# schematicEagle.net
KiCad netlist of a schematic drawn in EAGLE
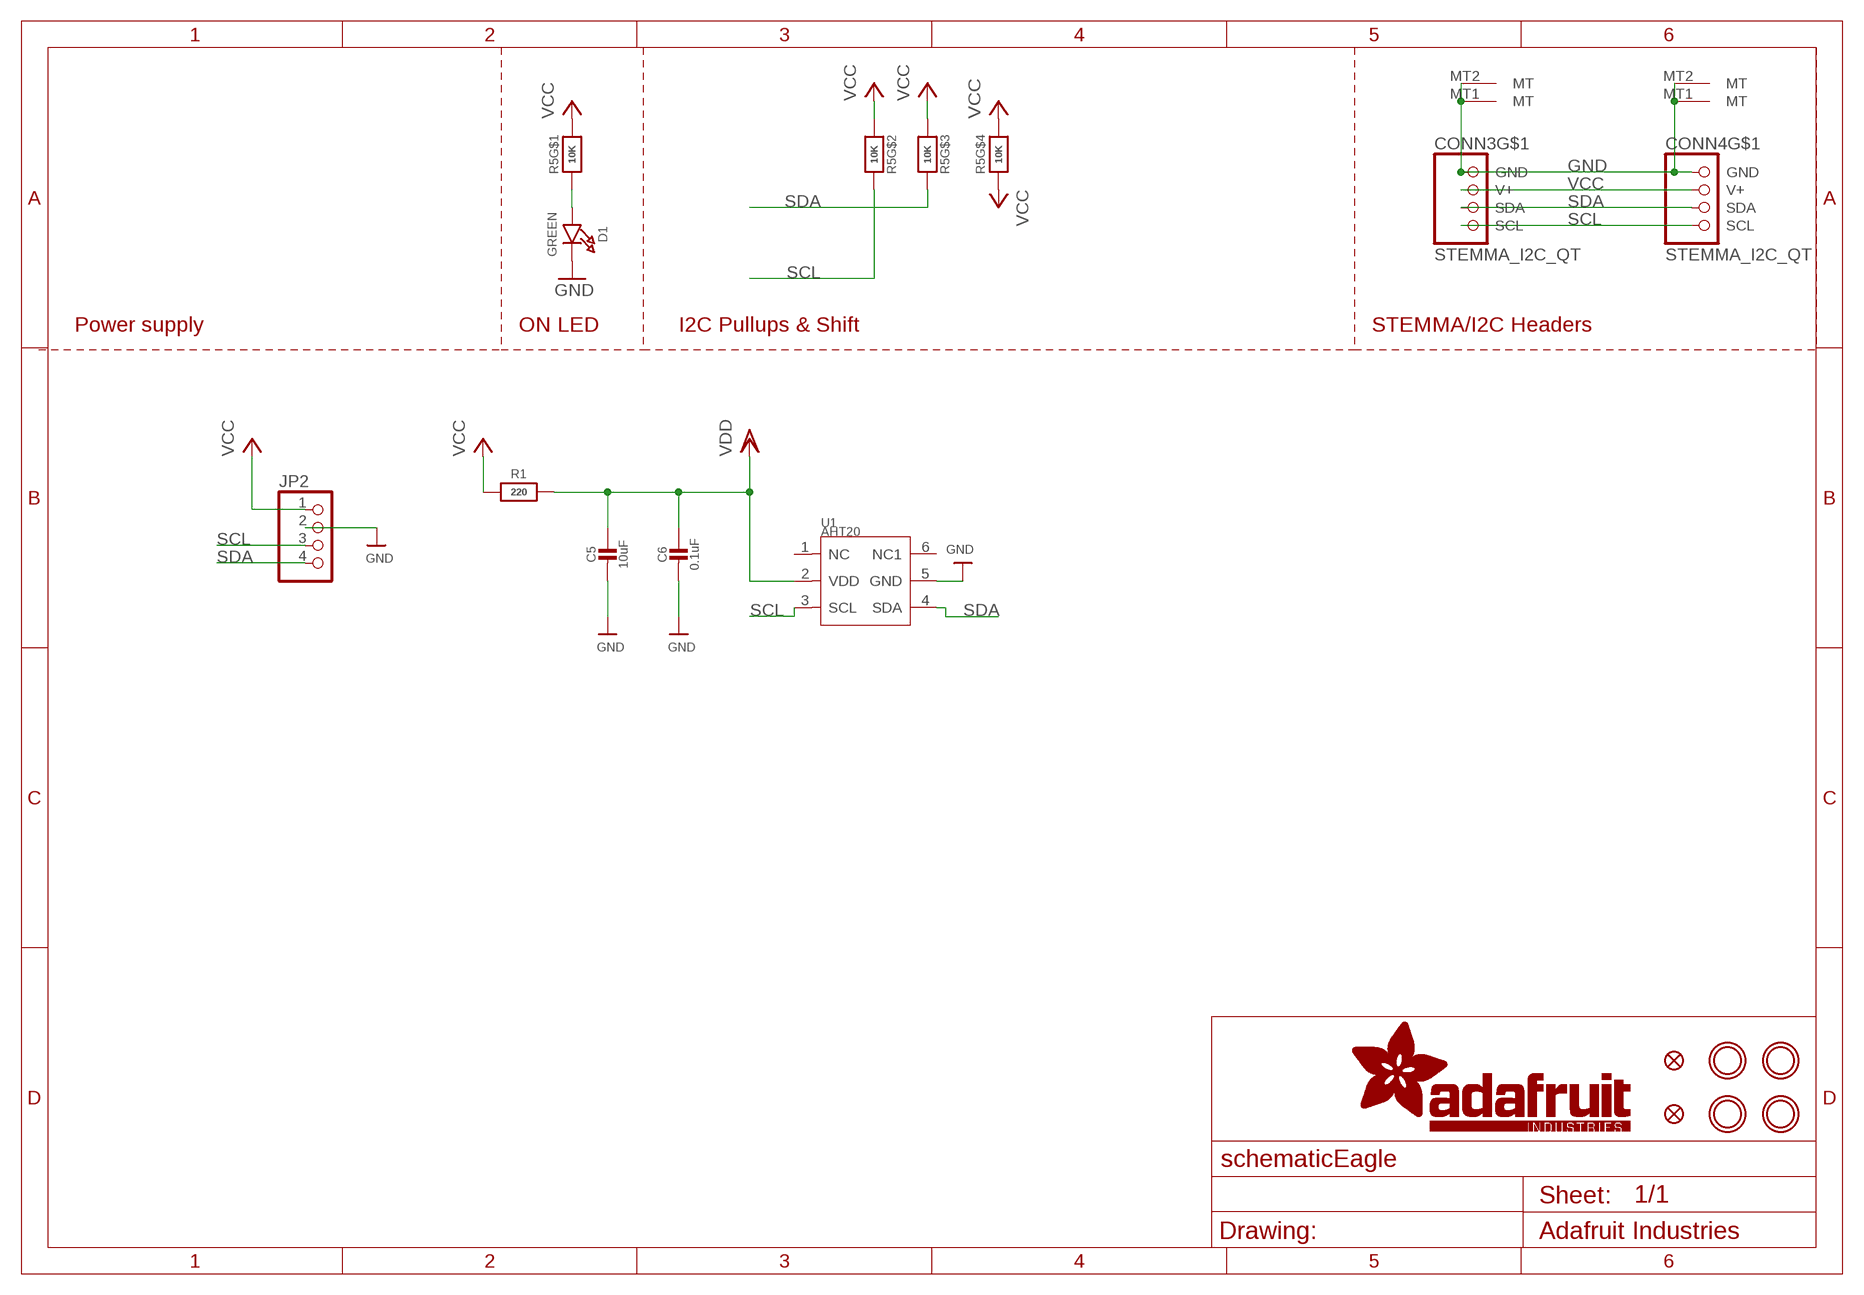
[diagram p0: schematic, sheet 1]

(export (version "E")
  (design (tool "Eeschema 10.0.6"))
  (components
    (comp (ref "C5")
      (value "10uF")
      (footprint "eagle-import:0805-NO")
      (libsource (lib "eagle-import") (part "CAP_CERAMIC0805-NOOUTLINE"))
    )
    (comp (ref "C6")
      (value "0.1uF")
      (footprint "eagle-import:0603-NO")
      (libsource (lib "eagle-import") (part "CAP_CERAMIC0603_NO"))
    )
    (comp (ref "CONN3")
      (value "STEMMA_I2C_QT")
      (footprint "eagle-import:JST_SH4")
      (libsource (lib "eagle-import") (part "STEMMA_I2C_QT"))
    )
    (comp (ref "CONN4")
      (value "STEMMA_I2C_QT")
      (footprint "eagle-import:JST_SH4")
      (libsource (lib "eagle-import") (part "STEMMA_I2C_QT"))
    )
    (comp (ref "D1")
      (value "GREEN")
      (footprint "eagle-import:CHIPLED_0603_NOOUTLINE")
      (libsource (lib "eagle-import") (part "LED0603_NOOUTLINE"))
    )
    (comp (ref "FID3")
      (value "FIDUCIAL_1MM")
      (footprint "eagle-import:FIDUCIAL_1MM")
      (libsource (lib "eagle-import") (part "FIDUCIAL_1MM"))
    )
    (comp (ref "FID4")
      (value "FIDUCIAL_1MM")
      (footprint "eagle-import:FIDUCIAL_1MM")
      (libsource (lib "eagle-import") (part "FIDUCIAL_1MM"))
    )
    (comp (ref "JP2")
      (value "HEADER-1X476MIL")
      (footprint "eagle-import:1X04_ROUND_76")
      (libsource (lib "eagle-import") (part "HEADER-1X476MIL"))
    )
    (comp (ref "R1")
      (value "220")
      (footprint "eagle-import:0603-NO")
      (libsource (lib "eagle-import") (part "RESISTOR_0603_NOOUT"))
    )
    (comp (ref "R5")
      (value "10K")
      (footprint "eagle-import:RESPACK_4X0603")
      (libsource (lib "eagle-import") (part "RESISTOR_4PACK"))
    )
    (comp (ref "U$19")
      (value "MOUNTINGHOLE2.5")
      (footprint "eagle-import:MOUNTINGHOLE_2.5_PLATED")
      (libsource (lib "eagle-import") (part "MOUNTINGHOLE2.5"))
    )
    (comp (ref "U$20")
      (value "MOUNTINGHOLE2.5")
      (footprint "eagle-import:MOUNTINGHOLE_2.5_PLATED")
      (libsource (lib "eagle-import") (part "MOUNTINGHOLE2.5"))
    )
    (comp (ref "U$22")
      (value "MOUNTINGHOLE2.5")
      (footprint "eagle-import:MOUNTINGHOLE_2.5_PLATED")
      (libsource (lib "eagle-import") (part "MOUNTINGHOLE2.5"))
    )
    (comp (ref "U$25")
      (value "MOUNTINGHOLE2.5")
      (footprint "eagle-import:MOUNTINGHOLE_2.5_PLATED")
      (libsource (lib "eagle-import") (part "MOUNTINGHOLE2.5"))
    )
    (comp (ref "U1")
      (value "AHT20")
      (footprint "eagle-import:SNR6-1.0-3X3X1MM")
      (libsource (lib "eagle-import") (part "SENSOR-AHT20"))
    )
  )
  (nets
    (net (code "1") (name "/SCL") (class "Default")
      (node (ref "CONN3") (pin "4") (pinfunction "SCL_4") (pintype "passive"))
      (node (ref "CONN4") (pin "4") (pinfunction "SCL_4") (pintype "passive"))
      (node (ref "JP2") (pin "3") (pinfunction "3_3") (pintype "passive"))
      (node (ref "R5") (pin "7") (pinfunction "2_7") (pintype "passive"))
      (node (ref "U1") (pin "3") (pinfunction "SCL_3") (pintype "bidirectional"))
    )
    (net (code "2") (name "/SDA") (class "Default")
      (node (ref "CONN3") (pin "3") (pinfunction "SDA_3") (pintype "passive"))
      (node (ref "CONN4") (pin "3") (pinfunction "SDA_3") (pintype "passive"))
      (node (ref "JP2") (pin "4") (pinfunction "4_4") (pintype "passive"))
      (node (ref "R5") (pin "6") (pinfunction "2_6") (pintype "passive"))
      (node (ref "U1") (pin "4") (pinfunction "SDA_4") (pintype "bidirectional"))
    )
    (net (code "3") (name "GND") (class "Default")
      (node (ref "C5") (pin "2") (pinfunction "2_2") (pintype "passive"))
      (node (ref "C6") (pin "2") (pinfunction "2_2") (pintype "passive"))
      (node (ref "CONN3") (pin "1") (pinfunction "GND_1") (pintype "passive"))
      (node (ref "CONN3") (pin "MT1") (pinfunction "MT_MT1") (pintype "bidirectional"))
      (node (ref "CONN3") (pin "MT2") (pinfunction "MT_MT2") (pintype "bidirectional"))
      (node (ref "CONN4") (pin "1") (pinfunction "GND_1") (pintype "passive"))
      (node (ref "CONN4") (pin "MT1") (pinfunction "MT_MT1") (pintype "bidirectional"))
      (node (ref "CONN4") (pin "MT2") (pinfunction "MT_MT2") (pintype "bidirectional"))
      (node (ref "D1") (pin "C") (pinfunction "C_C") (pintype "passive"))
      (node (ref "JP2") (pin "2") (pinfunction "2_2") (pintype "passive"))
      (node (ref "U1") (pin "5") (pinfunction "GND_5") (pintype "bidirectional"))
    )
    (net (code "4") (name "Net-(D1-PadA)") (class "Default")
      (node (ref "D1") (pin "A") (pinfunction "A_A") (pintype "passive"))
      (node (ref "R5") (pin "1") (pinfunction "1_1") (pintype "passive"))
    )
    (net (code "5") (name "VCC") (class "Default")
      (node (ref "CONN3") (pin "2") (pinfunction "V+_2") (pintype "passive"))
      (node (ref "CONN4") (pin "2") (pinfunction "V+_2") (pintype "passive"))
      (node (ref "JP2") (pin "1") (pinfunction "1_1") (pintype "passive"))
      (node (ref "R1") (pin "1") (pinfunction "1_1") (pintype "passive"))
      (node (ref "R5") (pin "2") (pinfunction "1_2") (pintype "passive"))
      (node (ref "R5") (pin "3") (pinfunction "1_3") (pintype "passive"))
      (node (ref "R5") (pin "4") (pinfunction "1_4") (pintype "passive"))
      (node (ref "R5") (pin "5") (pinfunction "2_5") (pintype "passive"))
      (node (ref "R5") (pin "8") (pinfunction "2_8") (pintype "passive"))
    )
    (net (code "6") (name "VDD") (class "Default")
      (node (ref "C5") (pin "1") (pinfunction "1_1") (pintype "passive"))
      (node (ref "C6") (pin "1") (pinfunction "1_1") (pintype "passive"))
      (node (ref "R1") (pin "2") (pinfunction "2_2") (pintype "passive"))
      (node (ref "U1") (pin "2") (pinfunction "VDD_2") (pintype "bidirectional"))
    )
    (net (code "7") (name "unconnected-(U1-NC-Pad1)") (class "Default")
      (node (ref "U1") (pin "1") (pinfunction "NC_1") (pintype "bidirectional"))
    )
    (net (code "8") (name "unconnected-(U1-NC1-Pad6)") (class "Default")
      (node (ref "U1") (pin "6") (pinfunction "NC1_6") (pintype "bidirectional"))
    )
  )
)
